# Minized.net
KiCad netlist of a schematic drawn in Altium Designer
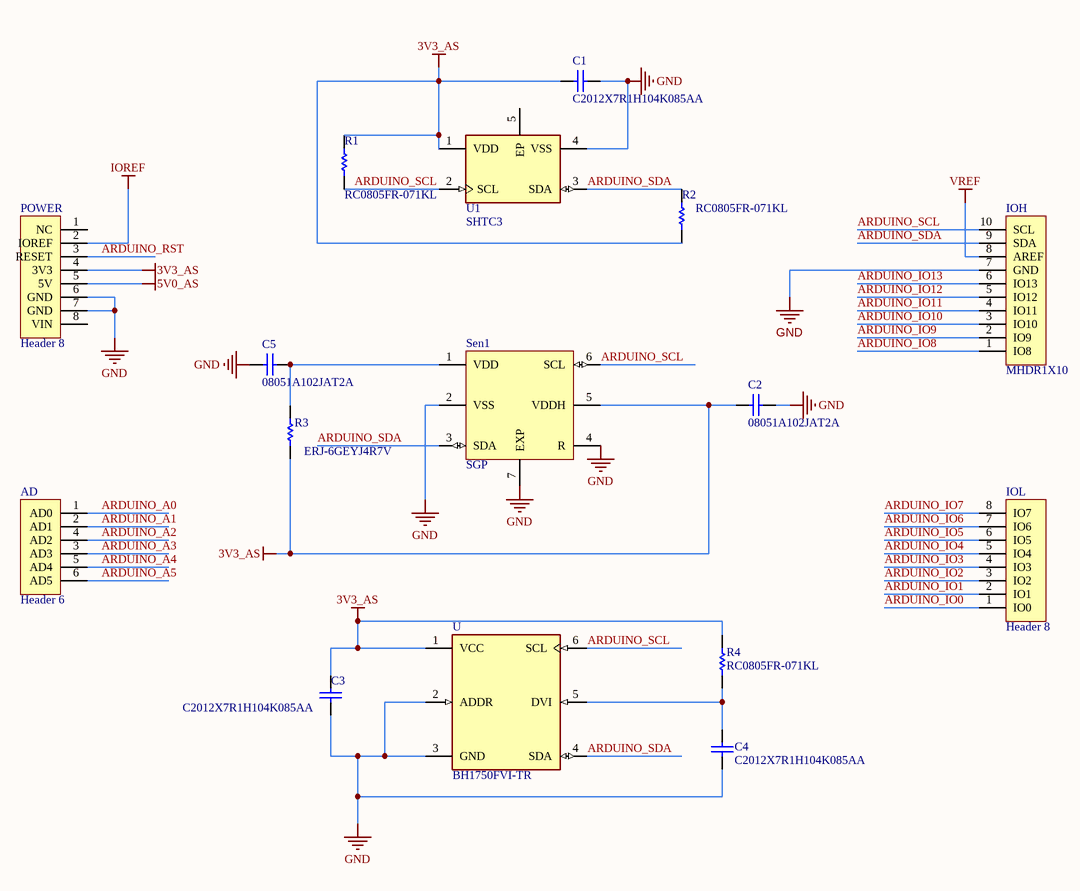
[diagram p0: Minized.SchDoc]

(export (version "E")
  (design (tool "Eeschema 10.0.6"))
  (components
    (comp (ref "AD")
      (value "Header 6")
      (footprint "HDR1X6")
      (description "Header, 6-Pin")
      (fields (field (name "PUBLISHER") "Altium Limited"))
      (libsource (lib "Miscellaneous Connectors") (part "Header 6"))
    )
    (comp (ref "C1")
      (value "C2012X7R1H104K085AA")
      (footprint "CAPC2013X145X20LL20")
      (description "Chip Capacitor, 0.1 uF, +/- 10%, 50 V, -55 to 125 degC, 0805 (2012 Metric), RoHS, Tape and Reel")
      (fields (field (name "MANUFACTURER") "TDK") (field (name "VOLTAGE") "50V"))
      (libsource (lib "Altium Content Vault") (part "CAP-NP-2"))
    )
    (comp (ref "C2")
      (value "08051A102JAT2A")
      (footprint "CAPC2013X140X50NL20T25")
      (fields (field (name "MANUFACTURER") "AVX Interconnect / Elco"))
      (libsource (lib "Altium Content Vault") (part "CAP"))
    )
    (comp (ref "C3")
      (value "C2012X7R1H104K085AA")
      (footprint "CAPC2013X145X20LL20")
      (description "Chip Capacitor, 0.1 uF, +/- 10%, 50 V, -55 to 125 degC, 0805 (2012 Metric), RoHS, Tape and Reel")
      (fields (field (name "MANUFACTURER") "TDK") (field (name "VOLTAGE") "50V"))
      (libsource (lib "Altium Content Vault") (part "CAP-NP-2"))
    )
    (comp (ref "C4")
      (value "C2012X7R1H104K085AA")
      (footprint "CAPC2013X145X20LL20")
      (description "Chip Capacitor, 0.1 uF, +/- 10%, 50 V, -55 to 125 degC, 0805 (2012 Metric), RoHS, Tape and Reel")
      (fields (field (name "MANUFACTURER") "TDK") (field (name "VOLTAGE") "50V"))
      (libsource (lib "Altium Content Vault") (part "CAP-NP-2"))
    )
    (comp (ref "C5")
      (value "08051A102JAT2A")
      (footprint "CAPC2013X140X50NL20T25")
      (fields (field (name "MANUFACTURER") "AVX Interconnect / Elco"))
      (libsource (lib "Altium Content Vault") (part "CAP"))
    )
    (comp (ref "IOH")
      (value "MHDR1X10")
      (footprint "MHDR1X10")
      (description "Header, 10-Pin")
      (fields (field (name "PUBLISHER") "Altium Limited"))
      (libsource (lib "Miscellaneous Connectors") (part "MHDR1X10"))
    )
    (comp (ref "IOL")
      (value "Header 8")
      (footprint "HDR1X8")
      (description "Header, 8-Pin")
      (fields (field (name "PUBLISHER") "Altium Limited"))
      (libsource (lib "") (part "Header 8_1"))
    )
    (comp (ref "POWER")
      (value "Header 8")
      (footprint "HDR1X8")
      (description "Header, 8-Pin")
      (fields (field (name "PUBLISHER") "Altium Limited"))
      (libsource (lib "Miscellaneous Connectors") (part "Header 8"))
    )
    (comp (ref "R1")
      (value "RC0805FR-071KL")
      (footprint "RESC2013X60X35ML10T20")
      (description "Chip Resistor, 1 KOhm, +/- 1%, 125 mW, -55 to 155 degC, 0805 (2012 Metric), RoHS, Tape and Reel")
      (fields (field (name "TOLERANCE") "1%") (field (name "MANUFACTURER") "Yageo"))
      (libsource (lib "Altium Content Vault") (part "RES-2"))
    )
    (comp (ref "R2")
      (value "RC0805FR-071KL")
      (footprint "RESC2013X60X35ML10T20")
      (description "Chip Resistor, 1 KOhm, +/- 1%, 125 mW, -55 to 155 degC, 0805 (2012 Metric), RoHS, Tape and Reel")
      (fields (field (name "TOLERANCE") "1%") (field (name "MANUFACTURER") "Yageo"))
      (libsource (lib "Altium Content Vault") (part "RES-2"))
    )
    (comp (ref "R3")
      (value "ERJ-6GEYJ4R7V")
      (footprint "RESC2013X70X40LL20T20")
      (fields (field (name "MANUFACTURER") "Panasonic"))
      (libsource (lib "Altium Content Vault") (part "RES"))
    )
    (comp (ref "R4")
      (value "RC0805FR-071KL")
      (footprint "RESC2013X60X35ML10T20")
      (description "Chip Resistor, 1 KOhm, +/- 1%, 125 mW, -55 to 155 degC, 0805 (2012 Metric), RoHS, Tape and Reel")
      (fields (field (name "TOLERANCE") "1%") (field (name "MANUFACTURER") "Yageo"))
      (libsource (lib "Altium Content Vault") (part "RES-2"))
    )
    (comp (ref "Sen1") (value "SGP") (footprint "SGPx4x") (libsource (lib "SGP40") (part "SGP")))
    (comp (ref "U")
      (value "BH1750FVI-TR")
      (footprint "XDCR_BH1750FVI-TR")
      (description "Optical Sensor Ambient 560nm IÂ²C 6-SMD, Flat Lead Exposed Pad")
      (fields (field (name "MF") "Rohm"))
      (libsource (lib "BH1750FVI-TR") (part "BH1750FVI-TR"))
    )
    (comp (ref "U1")
      (value "SHTC3")
      (footprint "FP-SHTC3-MFG")
      (description "SENSOR HUMI/TEMP I2C 2% SMD")
      (fields
        (field (name "MANUFACTURER") "Sensirion")
        (field (name "OCTOPART") "https://octopart.com/shtc3-sensirion-91912225")
      )
      (libsource (lib "Altium Content Vault") (part "92e21da4ceb1e434b50171ab113565b"))
    )
  )
  (nets
    (net (code "1") (name "/ARDUINO_A0") (class "Default")
      (node (ref "AD") (pin "1") (pinfunction "AD0_1") (pintype "passive"))
    )
    (net (code "2") (name "/ARDUINO_A1") (class "Default")
      (node (ref "AD") (pin "2") (pinfunction "AD1_2") (pintype "passive"))
    )
    (net (code "3") (name "/ARDUINO_A2") (class "Default")
      (node (ref "AD") (pin "4") (pinfunction "AD2_4") (pintype "passive"))
    )
    (net (code "4") (name "/ARDUINO_A3") (class "Default")
      (node (ref "AD") (pin "3") (pinfunction "AD3_3") (pintype "passive"))
    )
    (net (code "5") (name "/ARDUINO_A4") (class "Default")
      (node (ref "AD") (pin "5") (pinfunction "AD4_5") (pintype "passive"))
    )
    (net (code "6") (name "/ARDUINO_A5") (class "Default")
      (node (ref "AD") (pin "6") (pinfunction "AD5_6") (pintype "passive"))
    )
    (net (code "7") (name "/ARDUINO_IO0") (class "Default")
      (node (ref "IOL") (pin "1") (pinfunction "IO0_1") (pintype "passive"))
    )
    (net (code "8") (name "/ARDUINO_IO1") (class "Default")
      (node (ref "IOL") (pin "2") (pinfunction "IO1_2") (pintype "passive"))
    )
    (net (code "9") (name "/ARDUINO_IO2") (class "Default")
      (node (ref "IOL") (pin "3") (pinfunction "IO2_3") (pintype "passive"))
    )
    (net (code "10") (name "/ARDUINO_IO3") (class "Default")
      (node (ref "IOL") (pin "4") (pinfunction "IO3_4") (pintype "passive"))
    )
    (net (code "11") (name "/ARDUINO_IO4") (class "Default")
      (node (ref "IOL") (pin "5") (pinfunction "IO4_5") (pintype "passive"))
    )
    (net (code "12") (name "/ARDUINO_IO5") (class "Default")
      (node (ref "IOL") (pin "6") (pinfunction "IO5_6") (pintype "passive"))
    )
    (net (code "13") (name "/ARDUINO_IO6") (class "Default")
      (node (ref "IOL") (pin "7") (pinfunction "IO6_7") (pintype "passive"))
    )
    (net (code "14") (name "/ARDUINO_IO7") (class "Default")
      (node (ref "IOL") (pin "8") (pinfunction "IO7_8") (pintype "passive"))
    )
    (net (code "15") (name "/ARDUINO_IO8") (class "Default")
      (node (ref "IOH") (pin "1") (pinfunction "IO8_1") (pintype "passive"))
    )
    (net (code "16") (name "/ARDUINO_IO9") (class "Default")
      (node (ref "IOH") (pin "2") (pinfunction "IO9_2") (pintype "passive"))
    )
    (net (code "17") (name "/ARDUINO_IO10") (class "Default")
      (node (ref "IOH") (pin "3") (pinfunction "IO10_3") (pintype "passive"))
    )
    (net (code "18") (name "/ARDUINO_IO11") (class "Default")
      (node (ref "IOH") (pin "4") (pinfunction "IO11_4") (pintype "passive"))
    )
    (net (code "19") (name "/ARDUINO_IO12") (class "Default")
      (node (ref "IOH") (pin "5") (pinfunction "IO12_5") (pintype "passive"))
    )
    (net (code "20") (name "/ARDUINO_IO13") (class "Default")
      (node (ref "IOH") (pin "6") (pinfunction "IO13_6") (pintype "passive"))
    )
    (net (code "21") (name "/ARDUINO_RST") (class "Default")
      (node (ref "POWER") (pin "3") (pinfunction "RESET_3") (pintype "passive"))
    )
    (net (code "22") (name "/ARDUINO_SCL") (class "Default")
      (node (ref "IOH") (pin "10") (pinfunction "SCL_10") (pintype "passive"))
      (node (ref "R1") (pin "1") (pinfunction "1_1") (pintype "passive"))
      (node (ref "Sen1") (pin "6") (pinfunction "SCL_6") (pintype "bidirectional"))
      (node (ref "U") (pin "6") (pinfunction "SCL_6") (pintype "input"))
      (node (ref "U1") (pin "2") (pinfunction "SCL_2") (pintype "input"))
    )
    (net (code "23") (name "/ARDUINO_SDA") (class "Default")
      (node (ref "IOH") (pin "9") (pinfunction "SDA_9") (pintype "passive"))
      (node (ref "R2") (pin "2") (pinfunction "2_2") (pintype "passive"))
      (node (ref "Sen1") (pin "3") (pinfunction "SDA_3") (pintype "bidirectional"))
      (node (ref "U") (pin "4") (pinfunction "SDA_4") (pintype "bidirectional"))
      (node (ref "U1") (pin "3") (pinfunction "SDA_3") (pintype "bidirectional"))
    )
    (net (code "24") (name "3V3_AS") (class "Default")
      (node (ref "C1") (pin "1") (pinfunction "1_1") (pintype "passive"))
      (node (ref "C2") (pin "2") (pinfunction "2_2") (pintype "passive"))
      (node (ref "C3") (pin "2") (pinfunction "2_2") (pintype "passive"))
      (node (ref "POWER") (pin "4") (pinfunction "3V3_4") (pintype "passive"))
      (node (ref "R1") (pin "2") (pinfunction "2_2") (pintype "passive"))
      (node (ref "R2") (pin "1") (pinfunction "1_1") (pintype "passive"))
      (node (ref "R3") (pin "1") (pinfunction "1_1") (pintype "passive"))
      (node (ref "R4") (pin "2") (pinfunction "2_2") (pintype "passive"))
      (node (ref "Sen1") (pin "5") (pinfunction "VDDH_5") (pintype "power_in"))
      (node (ref "U") (pin "1") (pinfunction "VCC_1") (pintype "power_in"))
      (node (ref "U1") (pin "1") (pinfunction "VDD_1") (pintype "power_in"))
    )
    (net (code "25") (name "5V0_AS") (class "Default")
      (node (ref "POWER") (pin "5") (pinfunction "5V_5") (pintype "passive"))
    )
    (net (code "26") (name "GND") (class "Default")
      (node (ref "C1") (pin "2") (pinfunction "2_2") (pintype "passive"))
      (node (ref "C2") (pin "1") (pinfunction "1_1") (pintype "passive"))
      (node (ref "C3") (pin "1") (pinfunction "1_1") (pintype "passive"))
      (node (ref "C4") (pin "1") (pinfunction "1_1") (pintype "passive"))
      (node (ref "C5") (pin "1") (pinfunction "1_1") (pintype "passive"))
      (node (ref "IOH") (pin "7") (pinfunction "GND_7") (pintype "passive"))
      (node (ref "POWER") (pin "6") (pinfunction "GND_6") (pintype "passive"))
      (node (ref "POWER") (pin "7") (pinfunction "GND_7") (pintype "passive"))
      (node (ref "Sen1") (pin "2") (pinfunction "VSS_2") (pintype "power_in"))
      (node (ref "Sen1") (pin "4") (pinfunction "R_4") (pintype "passive"))
      (node (ref "Sen1") (pin "7") (pinfunction "EXP_7") (pintype "power_in"))
      (node (ref "U") (pin "2") (pinfunction "ADDR_2") (pintype "input"))
      (node (ref "U") (pin "3") (pinfunction "GND_3") (pintype "power_in"))
      (node (ref "U1") (pin "4") (pinfunction "VSS_4") (pintype "power_in"))
    )
    (net (code "27") (name "IOREF") (class "Default")
      (node (ref "POWER") (pin "2") (pinfunction "IOREF_2") (pintype "passive"))
    )
    (net (code "28") (name "Net-(Sen1-VDD)") (class "Default")
      (node (ref "C5") (pin "2") (pinfunction "2_2") (pintype "passive"))
      (node (ref "R3") (pin "2") (pinfunction "2_2") (pintype "passive"))
      (node (ref "Sen1") (pin "1") (pinfunction "VDD_1") (pintype "power_in"))
    )
    (net (code "29") (name "Net-(U-DVI)") (class "Default")
      (node (ref "C4") (pin "2") (pinfunction "2_2") (pintype "passive"))
      (node (ref "R4") (pin "1") (pinfunction "1_1") (pintype "passive"))
      (node (ref "U") (pin "5") (pinfunction "DVI_5") (pintype "input"))
    )
    (net (code "30") (name "VREF") (class "Default")
      (node (ref "IOH") (pin "8") (pinfunction "AREF_8") (pintype "passive"))
    )
    (net (code "31") (name "unconnected-(POWER-NC-Pad1)") (class "Default")
      (node (ref "POWER") (pin "1") (pinfunction "NC_1") (pintype "passive"))
    )
    (net (code "32") (name "unconnected-(POWER-VIN-Pad8)") (class "Default")
      (node (ref "POWER") (pin "8") (pinfunction "VIN_8") (pintype "passive"))
    )
    (net (code "33") (name "unconnected-(U1-EP-Pad5)") (class "Default")
      (node (ref "U1") (pin "5") (pinfunction "EP_5") (pintype "power_in"))
    )
  )
)
